# h-bridge.net
KiCad netlist of a schematic drawn in EAGLE
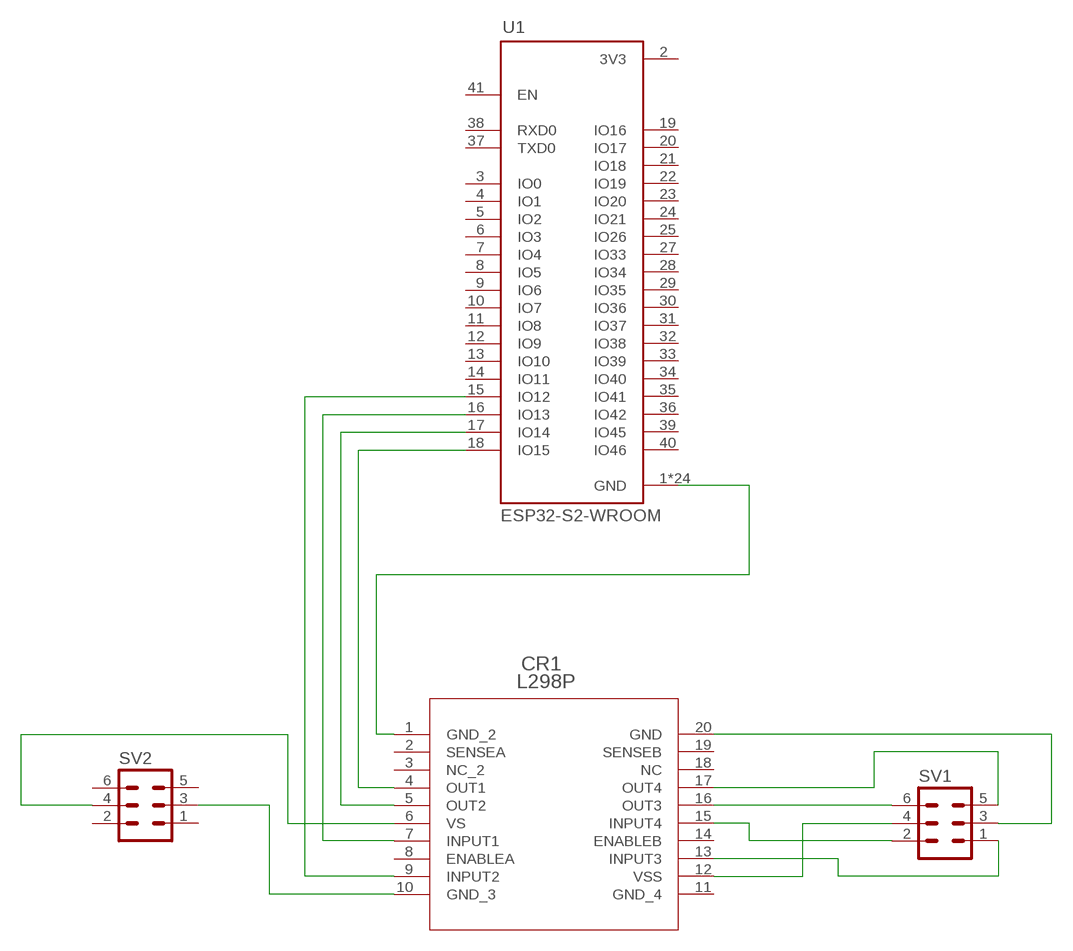
[diagram p0: schematic, sheet 1]

(export (version "E")
  (design (tool "Eeschema 10.0.6"))
  (components
    (comp (ref "CR1")
      (value "L298P")
      (footprint "eagle-import:POWERSO-20_STM")
      (fields (field (name "COPYRIGHT") "Copyright (C) 2022 Ultra Librarian. All rights reserved."))
      (libsource (lib "eagle-import") (part "L298P"))
    )
    (comp (ref "SV1")
      (value "ML6")
      (footprint "eagle-import:ML6")
      (libsource (lib "eagle-import") (part "ML6"))
    )
    (comp (ref "SV2")
      (value "ML6")
      (footprint "eagle-import:ML6")
      (libsource (lib "eagle-import") (part "ML6"))
    )
    (comp (ref "U1")
      (value "ESP32-S2-WROOM")
      (footprint "eagle-import:XCVR_ESP32-S2-WROOM")
      (fields (field (name "MF") "Espressif Systems"))
      (libsource (lib "eagle-import") (part "ESP32-S2-WROOM"))
    )
  )
  (nets
    (net (code "1") (name "/3V3") (class "Default")
      (node (ref "U1") (pin "2") (pinfunction "3V3_2") (pintype "power_in"))
    )
    (net (code "2") (name "Net-(CR1-GND)") (class "Default")
      (node (ref "CR1") (pin "20") (pinfunction "GND_20") (pintype "passive"))
      (node (ref "SV1") (pin "3") (pinfunction "3_3") (pintype "passive"))
    )
    (net (code "3") (name "Net-(CR1-GND_2)") (class "Default")
      (node (ref "CR1") (pin "1") (pinfunction "GND_2_1") (pintype "passive"))
      (node (ref "U1") (pin "1") (pinfunction "GND_1") (pintype "power_in"))
      (node (ref "U1") (pin "26") (pinfunction "GND_26") (pintype "power_in"))
      (node (ref "U1") (pin "42") (pinfunction "GND_42") (pintype "power_in"))
      (node (ref "U1") (pin "43.1") (pinfunction "GND_43.1") (pintype "power_in"))
      (node (ref "U1") (pin "43.10") (pinfunction "GND_43.10") (pintype "power_in"))
      (node (ref "U1") (pin "43.11") (pinfunction "GND_43.11") (pintype "power_in"))
      (node (ref "U1") (pin "43.12") (pinfunction "GND_43.12") (pintype "power_in"))
      (node (ref "U1") (pin "43.13") (pinfunction "GND_43.13") (pintype "power_in"))
      (node (ref "U1") (pin "43.14") (pinfunction "GND_43.14") (pintype "power_in"))
      (node (ref "U1") (pin "43.15") (pinfunction "GND_43.15") (pintype "power_in"))
      (node (ref "U1") (pin "43.16") (pinfunction "GND_43.16") (pintype "power_in"))
      (node (ref "U1") (pin "43.17") (pinfunction "GND_43.17") (pintype "power_in"))
      (node (ref "U1") (pin "43.18") (pinfunction "GND_43.18") (pintype "power_in"))
      (node (ref "U1") (pin "43.19") (pinfunction "GND_43.19") (pintype "power_in"))
      (node (ref "U1") (pin "43.2") (pinfunction "GND_43.2") (pintype "power_in"))
      (node (ref "U1") (pin "43.20") (pinfunction "GND_43.20") (pintype "power_in"))
      (node (ref "U1") (pin "43.21") (pinfunction "GND_43.21") (pintype "power_in"))
      (node (ref "U1") (pin "43.3") (pinfunction "GND_43.3") (pintype "power_in"))
      (node (ref "U1") (pin "43.4") (pinfunction "GND_43.4") (pintype "power_in"))
      (node (ref "U1") (pin "43.5") (pinfunction "GND_43.5") (pintype "power_in"))
      (node (ref "U1") (pin "43.6") (pinfunction "GND_43.6") (pintype "power_in"))
      (node (ref "U1") (pin "43.7") (pinfunction "GND_43.7") (pintype "power_in"))
      (node (ref "U1") (pin "43.8") (pinfunction "GND_43.8") (pintype "power_in"))
      (node (ref "U1") (pin "43.9") (pinfunction "GND_43.9") (pintype "power_in"))
    )
    (net (code "4") (name "Net-(CR1-GND_3)") (class "Default")
      (node (ref "CR1") (pin "10") (pinfunction "GND_3_10") (pintype "passive"))
      (node (ref "SV2") (pin "3") (pinfunction "3_3") (pintype "passive"))
    )
    (net (code "5") (name "Net-(CR1-INPUT1)") (class "Default")
      (node (ref "CR1") (pin "7") (pinfunction "INPUT1_7") (pintype "input"))
      (node (ref "U1") (pin "16") (pinfunction "IO13_16") (pintype "bidirectional"))
    )
    (net (code "6") (name "Net-(CR1-INPUT2)") (class "Default")
      (node (ref "CR1") (pin "9") (pinfunction "INPUT2_9") (pintype "input"))
      (node (ref "U1") (pin "15") (pinfunction "IO12_15") (pintype "bidirectional"))
    )
    (net (code "7") (name "Net-(CR1-INPUT3)") (class "Default")
      (node (ref "CR1") (pin "13") (pinfunction "INPUT3_13") (pintype "input"))
      (node (ref "SV1") (pin "1") (pinfunction "1_1") (pintype "passive"))
    )
    (net (code "8") (name "Net-(CR1-INPUT4)") (class "Default")
      (node (ref "CR1") (pin "15") (pinfunction "INPUT4_15") (pintype "input"))
      (node (ref "SV1") (pin "2") (pinfunction "2_2") (pintype "passive"))
    )
    (net (code "9") (name "Net-(CR1-OUT1)") (class "Default")
      (node (ref "CR1") (pin "4") (pinfunction "OUT1_4") (pintype "output"))
      (node (ref "U1") (pin "18") (pinfunction "IO15_18") (pintype "bidirectional"))
    )
    (net (code "10") (name "Net-(CR1-OUT2)") (class "Default")
      (node (ref "CR1") (pin "5") (pinfunction "OUT2_5") (pintype "output"))
      (node (ref "U1") (pin "17") (pinfunction "IO14_17") (pintype "bidirectional"))
    )
    (net (code "11") (name "Net-(CR1-OUT3)") (class "Default")
      (node (ref "CR1") (pin "16") (pinfunction "OUT3_16") (pintype "output"))
      (node (ref "SV1") (pin "6") (pinfunction "6_6") (pintype "passive"))
    )
    (net (code "12") (name "Net-(CR1-OUT4)") (class "Default")
      (node (ref "CR1") (pin "17") (pinfunction "OUT4_17") (pintype "output"))
      (node (ref "SV1") (pin "5") (pinfunction "5_5") (pintype "passive"))
    )
    (net (code "13") (name "Net-(CR1-VS)") (class "Default")
      (node (ref "CR1") (pin "6") (pinfunction "VS_6") (pintype "power_in"))
      (node (ref "SV2") (pin "4") (pinfunction "4_4") (pintype "passive"))
    )
    (net (code "14") (name "Net-(CR1-VSS)") (class "Default")
      (node (ref "CR1") (pin "12") (pinfunction "VSS_12") (pintype "power_in"))
      (node (ref "SV1") (pin "4") (pinfunction "4_4") (pintype "passive"))
    )
    (net (code "15") (name "unconnected-(CR1-ENABLEA-Pad8)") (class "Default")
      (node (ref "CR1") (pin "8") (pinfunction "ENABLEA_8") (pintype "input"))
    )
    (net (code "16") (name "unconnected-(CR1-ENABLEB-Pad14)") (class "Default")
      (node (ref "CR1") (pin "14") (pinfunction "ENABLEB_14") (pintype "input"))
    )
    (net (code "17") (name "unconnected-(CR1-GND_4-Pad11)") (class "Default")
      (node (ref "CR1") (pin "11") (pinfunction "GND_4_11") (pintype "passive"))
    )
    (net (code "18") (name "unconnected-(CR1-NC-Pad18)") (class "Default")
      (node (ref "CR1") (pin "18") (pinfunction "NC_18") (pintype "no_connect"))
    )
    (net (code "19") (name "unconnected-(CR1-NC_2-Pad3)") (class "Default")
      (node (ref "CR1") (pin "3") (pinfunction "NC_2_3") (pintype "no_connect"))
    )
    (net (code "20") (name "unconnected-(CR1-SENSEA-Pad2)") (class "Default")
      (node (ref "CR1") (pin "2") (pinfunction "SENSEA_2") (pintype "input"))
    )
    (net (code "21") (name "unconnected-(CR1-SENSEB-Pad19)") (class "Default")
      (node (ref "CR1") (pin "19") (pinfunction "SENSEB_19") (pintype "input"))
    )
    (net (code "22") (name "unconnected-(SV2-Pad1)") (class "Default")
      (node (ref "SV2") (pin "1") (pinfunction "1_1") (pintype "passive"))
    )
    (net (code "23") (name "unconnected-(SV2-Pad2)") (class "Default")
      (node (ref "SV2") (pin "2") (pinfunction "2_2") (pintype "passive"))
    )
    (net (code "24") (name "unconnected-(SV2-Pad5)") (class "Default")
      (node (ref "SV2") (pin "5") (pinfunction "5_5") (pintype "passive"))
    )
    (net (code "25") (name "unconnected-(SV2-Pad6)") (class "Default")
      (node (ref "SV2") (pin "6") (pinfunction "6_6") (pintype "passive"))
    )
    (net (code "26") (name "unconnected-(U1-EN-Pad41)") (class "Default")
      (node (ref "U1") (pin "41") (pinfunction "EN_41") (pintype "input"))
    )
    (net (code "27") (name "unconnected-(U1-IO0-Pad3)") (class "Default")
      (node (ref "U1") (pin "3") (pinfunction "IO0_3") (pintype "bidirectional"))
    )
    (net (code "28") (name "unconnected-(U1-IO1-Pad4)") (class "Default")
      (node (ref "U1") (pin "4") (pinfunction "IO1_4") (pintype "bidirectional"))
    )
    (net (code "29") (name "unconnected-(U1-IO2-Pad5)") (class "Default")
      (node (ref "U1") (pin "5") (pinfunction "IO2_5") (pintype "bidirectional"))
    )
    (net (code "30") (name "unconnected-(U1-IO3-Pad6)") (class "Default")
      (node (ref "U1") (pin "6") (pinfunction "IO3_6") (pintype "bidirectional"))
    )
    (net (code "31") (name "unconnected-(U1-IO4-Pad7)") (class "Default")
      (node (ref "U1") (pin "7") (pinfunction "IO4_7") (pintype "bidirectional"))
    )
    (net (code "32") (name "unconnected-(U1-IO5-Pad8)") (class "Default")
      (node (ref "U1") (pin "8") (pinfunction "IO5_8") (pintype "bidirectional"))
    )
    (net (code "33") (name "unconnected-(U1-IO6-Pad9)") (class "Default")
      (node (ref "U1") (pin "9") (pinfunction "IO6_9") (pintype "bidirectional"))
    )
    (net (code "34") (name "unconnected-(U1-IO7-Pad10)") (class "Default")
      (node (ref "U1") (pin "10") (pinfunction "IO7_10") (pintype "bidirectional"))
    )
    (net (code "35") (name "unconnected-(U1-IO8-Pad11)") (class "Default")
      (node (ref "U1") (pin "11") (pinfunction "IO8_11") (pintype "bidirectional"))
    )
    (net (code "36") (name "unconnected-(U1-IO9-Pad12)") (class "Default")
      (node (ref "U1") (pin "12") (pinfunction "IO9_12") (pintype "bidirectional"))
    )
    (net (code "37") (name "unconnected-(U1-IO10-Pad13)") (class "Default")
      (node (ref "U1") (pin "13") (pinfunction "IO10_13") (pintype "bidirectional"))
    )
    (net (code "38") (name "unconnected-(U1-IO11-Pad14)") (class "Default")
      (node (ref "U1") (pin "14") (pinfunction "IO11_14") (pintype "bidirectional"))
    )
    (net (code "39") (name "unconnected-(U1-IO16-Pad19)") (class "Default")
      (node (ref "U1") (pin "19") (pinfunction "IO16_19") (pintype "bidirectional"))
    )
    (net (code "40") (name "unconnected-(U1-IO17-Pad20)") (class "Default")
      (node (ref "U1") (pin "20") (pinfunction "IO17_20") (pintype "bidirectional"))
    )
    (net (code "41") (name "unconnected-(U1-IO18-Pad21)") (class "Default")
      (node (ref "U1") (pin "21") (pinfunction "IO18_21") (pintype "bidirectional"))
    )
    (net (code "42") (name "unconnected-(U1-IO19-Pad22)") (class "Default")
      (node (ref "U1") (pin "22") (pinfunction "IO19_22") (pintype "bidirectional"))
    )
    (net (code "43") (name "unconnected-(U1-IO20-Pad23)") (class "Default")
      (node (ref "U1") (pin "23") (pinfunction "IO20_23") (pintype "bidirectional"))
    )
    (net (code "44") (name "unconnected-(U1-IO21-Pad24)") (class "Default")
      (node (ref "U1") (pin "24") (pinfunction "IO21_24") (pintype "bidirectional"))
    )
    (net (code "45") (name "unconnected-(U1-IO26-Pad25)") (class "Default")
      (node (ref "U1") (pin "25") (pinfunction "IO26_25") (pintype "bidirectional"))
    )
    (net (code "46") (name "unconnected-(U1-IO33-Pad27)") (class "Default")
      (node (ref "U1") (pin "27") (pinfunction "IO33_27") (pintype "bidirectional"))
    )
    (net (code "47") (name "unconnected-(U1-IO34-Pad28)") (class "Default")
      (node (ref "U1") (pin "28") (pinfunction "IO34_28") (pintype "bidirectional"))
    )
    (net (code "48") (name "unconnected-(U1-IO35-Pad29)") (class "Default")
      (node (ref "U1") (pin "29") (pinfunction "IO35_29") (pintype "bidirectional"))
    )
    (net (code "49") (name "unconnected-(U1-IO36-Pad30)") (class "Default")
      (node (ref "U1") (pin "30") (pinfunction "IO36_30") (pintype "bidirectional"))
    )
    (net (code "50") (name "unconnected-(U1-IO37-Pad31)") (class "Default")
      (node (ref "U1") (pin "31") (pinfunction "IO37_31") (pintype "bidirectional"))
    )
    (net (code "51") (name "unconnected-(U1-IO38-Pad32)") (class "Default")
      (node (ref "U1") (pin "32") (pinfunction "IO38_32") (pintype "bidirectional"))
    )
    (net (code "52") (name "unconnected-(U1-IO39-Pad33)") (class "Default")
      (node (ref "U1") (pin "33") (pinfunction "IO39_33") (pintype "bidirectional"))
    )
    (net (code "53") (name "unconnected-(U1-IO40-Pad34)") (class "Default")
      (node (ref "U1") (pin "34") (pinfunction "IO40_34") (pintype "bidirectional"))
    )
    (net (code "54") (name "unconnected-(U1-IO41-Pad35)") (class "Default")
      (node (ref "U1") (pin "35") (pinfunction "IO41_35") (pintype "bidirectional"))
    )
    (net (code "55") (name "unconnected-(U1-IO42-Pad36)") (class "Default")
      (node (ref "U1") (pin "36") (pinfunction "IO42_36") (pintype "bidirectional"))
    )
    (net (code "56") (name "unconnected-(U1-IO45-Pad39)") (class "Default")
      (node (ref "U1") (pin "39") (pinfunction "IO45_39") (pintype "bidirectional"))
    )
    (net (code "57") (name "unconnected-(U1-IO46-Pad40)") (class "Default")
      (node (ref "U1") (pin "40") (pinfunction "IO46_40") (pintype "bidirectional"))
    )
    (net (code "58") (name "unconnected-(U1-RXD0-Pad38)") (class "Default")
      (node (ref "U1") (pin "38") (pinfunction "RXD0_38") (pintype "bidirectional"))
    )
    (net (code "59") (name "unconnected-(U1-TXD0-Pad37)") (class "Default")
      (node (ref "U1") (pin "37") (pinfunction "TXD0_37") (pintype "bidirectional"))
    )
  )
)
